# zmena_polarity_BDD_1.net
KiCad netlist of a schematic drawn in Altium Designer
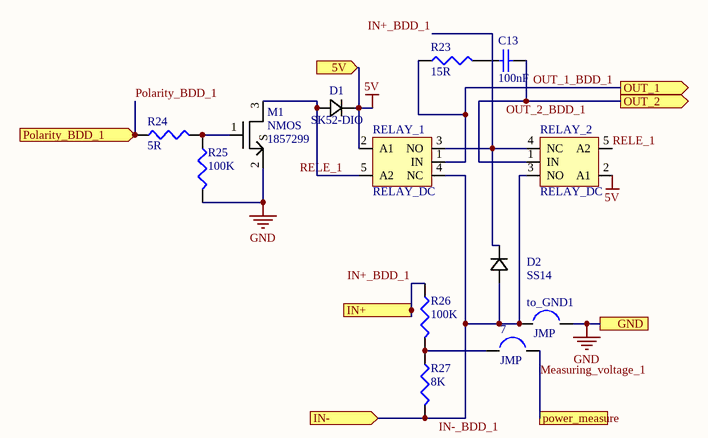
[diagram p0: zmena polarity_BDD_1.SchDoc]

(export (version "E")
  (design (tool "Eeschema 10.0.6"))
  (components
    (comp (ref "7") (value "JMP") (footprint "JMP") (libsource (lib "SamacSys") (part "JMP")))
    (comp (ref "C13")
      (value "100nF")
      (footprint "1608[0603]")
      (description "Capacitor (Semiconductor SIM Model)")
      (fields (field (name "PUBLISHER") "Altium Limited"))
      (libsource (lib "Miscellaneous Devices") (part "Cap Semi"))
    )
    (comp (ref "D1")
      (value "SK52-DIO")
      (footprint "D5A20V")
      (libsource (lib "SCH_Aquatec") (part "D_5A_20V"))
    )
    (comp (ref "D2") (value "SS14") (footprint "D5A20V") (libsource (lib "SCH_Aquatec") (part "D_5A_20V")))
    (comp (ref "M1")
      (value "NMOS")
      (footprint "SOT23")
      (fields (field (name "SUPPLIER PART NUMBER 1") "1857299"))
      (libsource (lib "SchematicLib_JP") (part "NMOS"))
    )
    (comp (ref "R23")
      (value "15R")
      (footprint "J1-0603")
      (description "Resistor")
      (fields (field (name "PUBLISHER") "Altium Limited"))
      (libsource (lib "Miscellaneous Devices") (part "Res3"))
    )
    (comp (ref "R24")
      (value "5R")
      (footprint "J1-0603")
      (description "Resistor")
      (fields (field (name "PUBLISHER") "Altium Limited"))
      (libsource (lib "Miscellaneous Devices") (part "Res3"))
    )
    (comp (ref "R25")
      (value "100K")
      (footprint "J1-0603")
      (description "Resistor")
      (fields (field (name "PUBLISHER") "Altium Limited"))
      (libsource (lib "Miscellaneous Devices") (part "Res3"))
    )
    (comp (ref "R26")
      (value "100K")
      (footprint "J1-0603")
      (description "Resistor")
      (fields (field (name "PUBLISHER") "Altium Limited"))
      (libsource (lib "Miscellaneous Devices") (part "Res3"))
    )
    (comp (ref "R27")
      (value "8K")
      (footprint "J1-0603")
      (description "Resistor")
      (fields (field (name "PUBLISHER") "Altium Limited"))
      (libsource (lib "Miscellaneous Devices") (part "Res3"))
    )
    (comp (ref "RELAY_1")
      (value "RELAY_DC")
      (footprint "RELAY_DC")
      (description "RM51-3011-85-1005")
      (libsource (lib "SCH_Aquatec") (part "RELAY_DC"))
    )
    (comp (ref "RELAY_2")
      (value "RELAY_DC")
      (footprint "RELAY_DC")
      (description "RM51-3011-85-1005")
      (libsource (lib "") (part "RELAY_DC_1"))
    )
    (comp (ref "to_GND1") (value "JMP") (footprint "JMP") (libsource (lib "SamacSys") (part "JMP")))
  )
  (nets
    (net (code "1") (name "/IN+_BDD_1") (class "Default")
      (node (ref "D2") (pin "1") (pinfunction "1_1") (pintype "passive"))
      (node (ref "R26") (pin "1") (pinfunction "1_1") (pintype "passive"))
      (node (ref "RELAY_1") (pin "3") (pinfunction "NO_3") (pintype "passive"))
      (node (ref "RELAY_2") (pin "4") (pinfunction "NC_4") (pintype "passive"))
    )
    (net (code "2") (name "/IN-_BDD_1") (class "Default")
      (node (ref "D2") (pin "2") (pinfunction "2_2") (pintype "passive"))
      (node (ref "R27") (pin "2") (pinfunction "2_2") (pintype "passive"))
      (node (ref "RELAY_1") (pin "4") (pinfunction "NC_4") (pintype "passive"))
      (node (ref "RELAY_2") (pin "3") (pinfunction "NO_3") (pintype "passive"))
      (node (ref "to_GND1") (pin "1") (pinfunction "1_1") (pintype "passive"))
    )
    (net (code "3") (name "/Measuring_voltage_1") (class "Default")
      (node (ref "7") (pin "2") (pinfunction "2_2") (pintype "passive"))
    )
    (net (code "4") (name "/OUT_1_BDD_1") (class "Default")
      (node (ref "R23") (pin "1") (pinfunction "1_1") (pintype "passive"))
      (node (ref "RELAY_1") (pin "1") (pinfunction "IN_1") (pintype "passive"))
    )
    (net (code "5") (name "/OUT_2_BDD_1") (class "Default")
      (node (ref "C13") (pin "2") (pinfunction "2_2") (pintype "passive"))
      (node (ref "RELAY_2") (pin "1") (pinfunction "IN_1") (pintype "passive"))
    )
    (net (code "6") (name "/Polarity_BDD_1") (class "Default")
      (node (ref "R24") (pin "1") (pinfunction "1_1") (pintype "passive"))
    )
    (net (code "7") (name "/RELE_1") (class "Default")
      (node (ref "D1") (pin "2") (pinfunction "2_2") (pintype "passive"))
      (node (ref "M1") (pin "3") (pinfunction "D_3") (pintype "passive"))
      (node (ref "RELAY_1") (pin "5") (pinfunction "A2_5") (pintype "passive"))
      (node (ref "RELAY_2") (pin "5") (pinfunction "A2_5") (pintype "passive"))
    )
    (net (code "8") (name "5V") (class "Default")
      (node (ref "D1") (pin "1") (pinfunction "1_1") (pintype "passive"))
      (node (ref "RELAY_1") (pin "2") (pinfunction "A1_2") (pintype "passive"))
      (node (ref "RELAY_2") (pin "2") (pinfunction "A1_2") (pintype "passive"))
    )
    (net (code "9") (name "GND") (class "Default")
      (node (ref "M1") (pin "2") (pinfunction "S_2") (pintype "passive"))
      (node (ref "R25") (pin "2") (pinfunction "2_2") (pintype "passive"))
      (node (ref "to_GND1") (pin "2") (pinfunction "2_2") (pintype "passive"))
    )
    (net (code "10") (name "Net-(7-Pad1)") (class "Default")
      (node (ref "7") (pin "1") (pinfunction "1_1") (pintype "passive"))
      (node (ref "R26") (pin "2") (pinfunction "2_2") (pintype "passive"))
      (node (ref "R27") (pin "1") (pinfunction "1_1") (pintype "passive"))
    )
    (net (code "11") (name "Net-(C13-Pad1)") (class "Default")
      (node (ref "C13") (pin "1") (pinfunction "1_1") (pintype "passive"))
      (node (ref "R23") (pin "2") (pinfunction "2_2") (pintype "passive"))
    )
    (net (code "12") (name "Net-(M1-G)") (class "Default")
      (node (ref "M1") (pin "1") (pinfunction "G_1") (pintype "passive"))
      (node (ref "R24") (pin "2") (pinfunction "2_2") (pintype "passive"))
      (node (ref "R25") (pin "1") (pinfunction "1_1") (pintype "passive"))
    )
  )
)
